# Front_left_lamp_v2.net
KiCad netlist of a schematic drawn in EAGLE
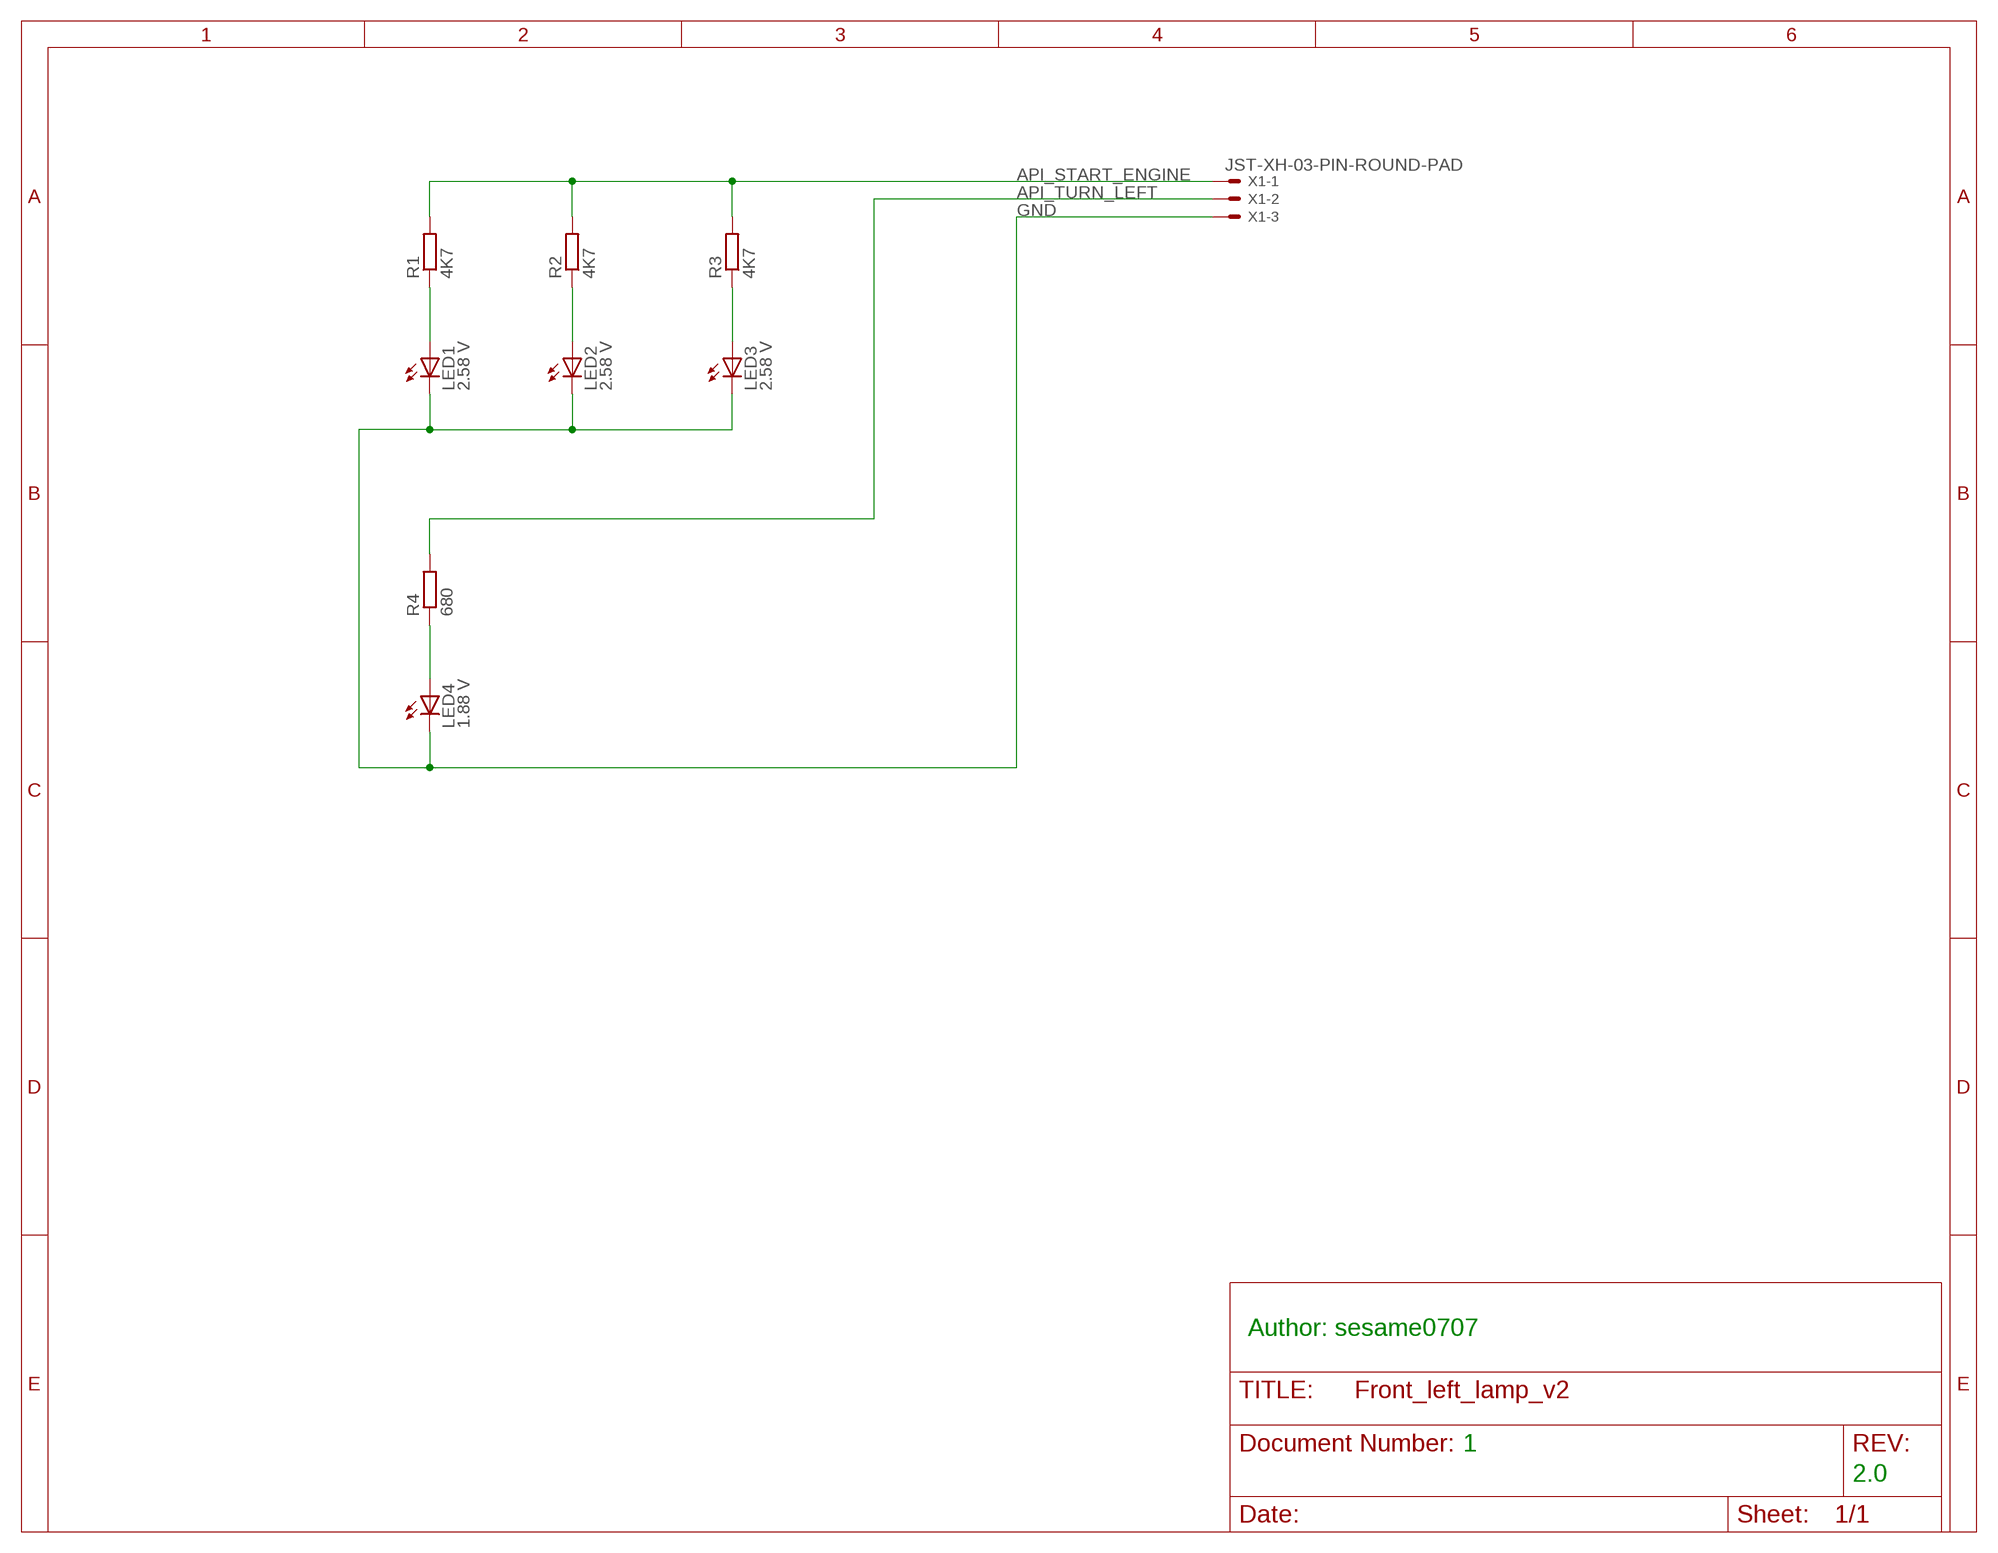
[diagram p0: schematic, sheet 1]

(export (version "E")
  (design (tool "Eeschema 10.0.6"))
  (components
    (comp (ref "LED1")
      (value "2.58 V")
      (footprint "eagle-import:LED5MM")
      (libsource (lib "eagle-import") (part "LED5MM"))
    )
    (comp (ref "LED2")
      (value "2.58 V")
      (footprint "eagle-import:LED5MM")
      (libsource (lib "eagle-import") (part "LED5MM"))
    )
    (comp (ref "LED3")
      (value "2.58 V")
      (footprint "eagle-import:LED5MM")
      (libsource (lib "eagle-import") (part "LED5MM"))
    )
    (comp (ref "LED4")
      (value "1.88 V")
      (footprint "eagle-import:LED5MM")
      (libsource (lib "eagle-import") (part "LED5MM"))
    )
    (comp (ref "R1")
      (value "4K7")
      (footprint "eagle-import:0204V")
      (libsource (lib "eagle-import") (part "R-EU_0204/2V"))
    )
    (comp (ref "R2")
      (value "4K7")
      (footprint "eagle-import:0204V")
      (libsource (lib "eagle-import") (part "R-EU_0204/2V"))
    )
    (comp (ref "R3")
      (value "4K7")
      (footprint "eagle-import:0204V")
      (libsource (lib "eagle-import") (part "R-EU_0204/2V"))
    )
    (comp (ref "R4")
      (value "680")
      (footprint "eagle-import:0204V")
      (libsource (lib "eagle-import") (part "R-EU_0204/2V"))
    )
    (comp (ref "X1")
      (value "JST-XH-03-PIN-ROUND-PAD")
      (footprint "eagle-import:JST-XH-03-PACKAGE-ROUND-PAD")
      (libsource (lib "eagle-import") (part "JST-XH-03-PIN-ROUND-PAD"))
    )
  )
  (nets
    (net (code "1") (name "/API_START_ENGINE") (class "Default")
      (node (ref "R1") (pin "2") (pinfunction "2_2") (pintype "passive"))
      (node (ref "R2") (pin "2") (pinfunction "2_2") (pintype "passive"))
      (node (ref "R3") (pin "2") (pinfunction "2_2") (pintype "passive"))
      (node (ref "X1") (pin "1") (pinfunction "S_1") (pintype "passive"))
    )
    (net (code "2") (name "/API_TURN_LEFT") (class "Default")
      (node (ref "R4") (pin "2") (pinfunction "2_2") (pintype "passive"))
      (node (ref "X1") (pin "2") (pinfunction "S_2") (pintype "passive"))
    )
    (net (code "3") (name "/GND") (class "Default")
      (node (ref "LED1") (pin "K") (pinfunction "C_K") (pintype "passive"))
      (node (ref "LED2") (pin "K") (pinfunction "C_K") (pintype "passive"))
      (node (ref "LED3") (pin "K") (pinfunction "C_K") (pintype "passive"))
      (node (ref "LED4") (pin "K") (pinfunction "C_K") (pintype "passive"))
      (node (ref "X1") (pin "3") (pinfunction "S_3") (pintype "passive"))
    )
    (net (code "4") (name "Net-(LED1-PadA)") (class "Default")
      (node (ref "LED1") (pin "A") (pinfunction "A_A") (pintype "passive"))
      (node (ref "R1") (pin "1") (pinfunction "1_1") (pintype "passive"))
    )
    (net (code "5") (name "Net-(LED2-PadA)") (class "Default")
      (node (ref "LED2") (pin "A") (pinfunction "A_A") (pintype "passive"))
      (node (ref "R2") (pin "1") (pinfunction "1_1") (pintype "passive"))
    )
    (net (code "6") (name "Net-(LED3-PadA)") (class "Default")
      (node (ref "LED3") (pin "A") (pinfunction "A_A") (pintype "passive"))
      (node (ref "R3") (pin "1") (pinfunction "1_1") (pintype "passive"))
    )
    (net (code "7") (name "Net-(LED4-PadA)") (class "Default")
      (node (ref "LED4") (pin "A") (pinfunction "A_A") (pintype "passive"))
      (node (ref "R4") (pin "1") (pinfunction "1_1") (pintype "passive"))
    )
  )
)
